# ffc_adapter.net
KiCad netlist of a schematic drawn in EAGLE
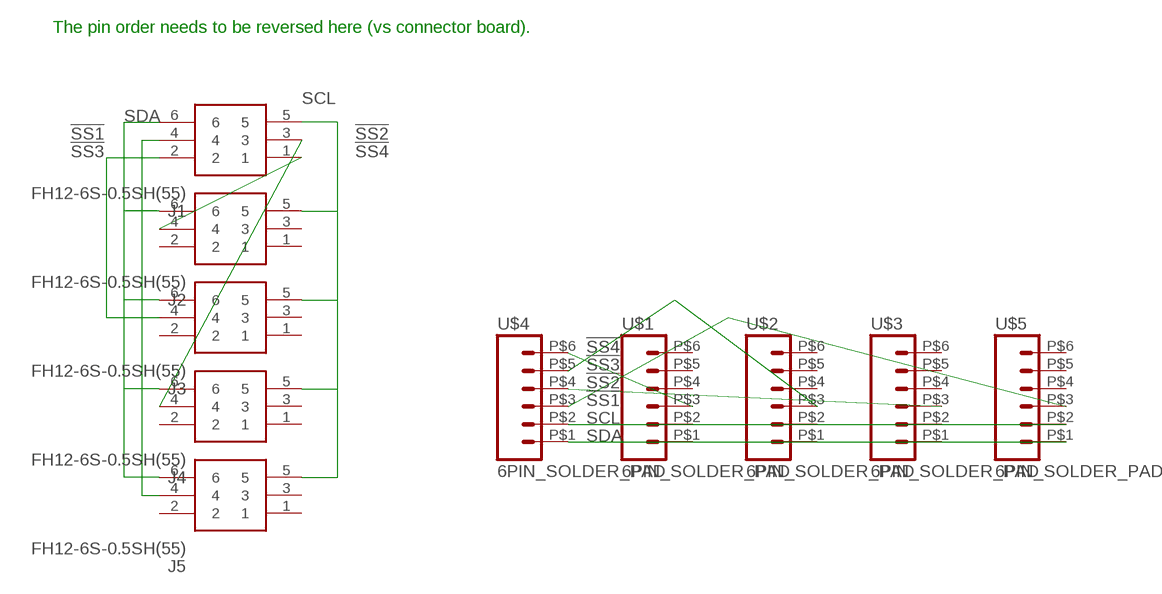
[diagram p0: schematic, sheet 1]

(export (version "E")
  (design (tool "Eeschema 10.0.6"))
  (components
    (comp (ref "J1")
      (value "FH12-6S-0.5SH(55)")
      (footprint "eagle-import:FH12-6S-0.5SH(55)_1")
      (fields
        (field (name "MOUSER_PART_NUMBER") "798-FH12-6S-0.5SH55")
        (field (name "RS_PART_NUMBER") "7388811P")
      )
      (libsource (lib "eagle-import") (part "FH12-6S-0.5SH(55)"))
    )
    (comp (ref "J2")
      (value "FH12-6S-0.5SH(55)")
      (footprint "eagle-import:FH12-6S-0.5SH(55)_1")
      (fields
        (field (name "MOUSER_PART_NUMBER") "798-FH12-6S-0.5SH55")
        (field (name "RS_PART_NUMBER") "7388811P")
      )
      (libsource (lib "eagle-import") (part "FH12-6S-0.5SH(55)"))
    )
    (comp (ref "J3")
      (value "FH12-6S-0.5SH(55)")
      (footprint "eagle-import:FH12-6S-0.5SH(55)_1")
      (fields
        (field (name "MOUSER_PART_NUMBER") "798-FH12-6S-0.5SH55")
        (field (name "RS_PART_NUMBER") "7388811P")
      )
      (libsource (lib "eagle-import") (part "FH12-6S-0.5SH(55)"))
    )
    (comp (ref "J4")
      (value "FH12-6S-0.5SH(55)")
      (footprint "eagle-import:FH12-6S-0.5SH(55)_1")
      (fields
        (field (name "MOUSER_PART_NUMBER") "798-FH12-6S-0.5SH55")
        (field (name "RS_PART_NUMBER") "7388811P")
      )
      (libsource (lib "eagle-import") (part "FH12-6S-0.5SH(55)"))
    )
    (comp (ref "J5")
      (value "FH12-6S-0.5SH(55)")
      (footprint "eagle-import:FH12-6S-0.5SH(55)_1")
      (fields
        (field (name "MOUSER_PART_NUMBER") "798-FH12-6S-0.5SH55")
        (field (name "RS_PART_NUMBER") "7388811P")
      )
      (libsource (lib "eagle-import") (part "FH12-6S-0.5SH(55)"))
    )
    (comp (ref "U$1")
      (value "6PIN_SOLDER_PAD")
      (footprint "eagle-import:6PIN_SOLDER_PAD")
      (libsource (lib "eagle-import") (part "6PIN_SOLDER_PAD"))
    )
    (comp (ref "U$2")
      (value "6PIN_SOLDER_PAD")
      (footprint "eagle-import:6PIN_SOLDER_PAD")
      (libsource (lib "eagle-import") (part "6PIN_SOLDER_PAD"))
    )
    (comp (ref "U$3")
      (value "6PIN_SOLDER_PAD")
      (footprint "eagle-import:6PIN_SOLDER_PAD")
      (libsource (lib "eagle-import") (part "6PIN_SOLDER_PAD"))
    )
    (comp (ref "U$4")
      (value "6PIN_SOLDER_PAD")
      (footprint "eagle-import:6PIN_SOLDER_PAD")
      (libsource (lib "eagle-import") (part "6PIN_SOLDER_PAD"))
    )
    (comp (ref "U$5")
      (value "6PIN_SOLDER_PAD")
      (footprint "eagle-import:6PIN_SOLDER_PAD")
      (libsource (lib "eagle-import") (part "6PIN_SOLDER_PAD"))
    )
  )
  (nets
    (net (code "1") (name "/SCL") (class "Default")
      (node (ref "J1") (pin "5") (pinfunction "5_5") (pintype "bidirectional"))
      (node (ref "J2") (pin "5") (pinfunction "5_5") (pintype "bidirectional"))
      (node (ref "J3") (pin "5") (pinfunction "5_5") (pintype "bidirectional"))
      (node (ref "J4") (pin "5") (pinfunction "5_5") (pintype "bidirectional"))
      (node (ref "J5") (pin "5") (pinfunction "5_5") (pintype "bidirectional"))
      (node (ref "U$1") (pin "P$2") (pinfunction "2_P$2") (pintype "passive"))
      (node (ref "U$2") (pin "P$2") (pinfunction "2_P$2") (pintype "passive"))
      (node (ref "U$3") (pin "P$2") (pinfunction "2_P$2") (pintype "passive"))
      (node (ref "U$4") (pin "P$2") (pinfunction "2_P$2") (pintype "passive"))
      (node (ref "U$5") (pin "P$2") (pinfunction "2_P$2") (pintype "passive"))
    )
    (net (code "2") (name "/SDA") (class "Default")
      (node (ref "J1") (pin "6") (pinfunction "6_6") (pintype "bidirectional"))
      (node (ref "J2") (pin "6") (pinfunction "6_6") (pintype "bidirectional"))
      (node (ref "J3") (pin "6") (pinfunction "6_6") (pintype "bidirectional"))
      (node (ref "J4") (pin "6") (pinfunction "6_6") (pintype "bidirectional"))
      (node (ref "J5") (pin "6") (pinfunction "6_6") (pintype "bidirectional"))
      (node (ref "U$1") (pin "P$1") (pinfunction "1_P$1") (pintype "passive"))
      (node (ref "U$2") (pin "P$1") (pinfunction "1_P$1") (pintype "passive"))
      (node (ref "U$3") (pin "P$1") (pinfunction "1_P$1") (pintype "passive"))
      (node (ref "U$4") (pin "P$1") (pinfunction "1_P$1") (pintype "passive"))
      (node (ref "U$5") (pin "P$1") (pinfunction "1_P$1") (pintype "passive"))
    )
    (net (code "3") (name "/~{SS1}") (class "Default")
      (node (ref "J1") (pin "4") (pinfunction "4_4") (pintype "bidirectional"))
      (node (ref "J5") (pin "4") (pinfunction "4_4") (pintype "bidirectional"))
      (node (ref "U$4") (pin "P$3") (pinfunction "3_P$3") (pintype "passive"))
      (node (ref "U$5") (pin "P$3") (pinfunction "3_P$3") (pintype "passive"))
    )
    (net (code "4") (name "/~{SS2}") (class "Default")
      (node (ref "J1") (pin "3") (pinfunction "3_3") (pintype "bidirectional"))
      (node (ref "J4") (pin "4") (pinfunction "4_4") (pintype "bidirectional"))
      (node (ref "U$3") (pin "P$3") (pinfunction "3_P$3") (pintype "passive"))
      (node (ref "U$4") (pin "P$4") (pinfunction "4_P$4") (pintype "passive"))
    )
    (net (code "5") (name "/~{SS3}") (class "Default")
      (node (ref "J1") (pin "2") (pinfunction "2_2") (pintype "bidirectional"))
      (node (ref "J3") (pin "4") (pinfunction "4_4") (pintype "bidirectional"))
      (node (ref "U$2") (pin "P$3") (pinfunction "3_P$3") (pintype "passive"))
      (node (ref "U$4") (pin "P$5") (pinfunction "5_P$5") (pintype "passive"))
    )
    (net (code "6") (name "/~{SS4}") (class "Default")
      (node (ref "J1") (pin "1") (pinfunction "1_1") (pintype "bidirectional"))
      (node (ref "J2") (pin "4") (pinfunction "4_4") (pintype "bidirectional"))
      (node (ref "U$1") (pin "P$3") (pinfunction "3_P$3") (pintype "passive"))
      (node (ref "U$4") (pin "P$6") (pinfunction "6_P$6") (pintype "passive"))
    )
    (net (code "7") (name "unconnected-(J2-Pad1)") (class "Default")
      (node (ref "J2") (pin "1") (pinfunction "1_1") (pintype "bidirectional"))
    )
    (net (code "8") (name "unconnected-(J2-Pad2)") (class "Default")
      (node (ref "J2") (pin "2") (pinfunction "2_2") (pintype "bidirectional"))
    )
    (net (code "9") (name "unconnected-(J2-Pad3)") (class "Default")
      (node (ref "J2") (pin "3") (pinfunction "3_3") (pintype "bidirectional"))
    )
    (net (code "10") (name "unconnected-(J3-Pad1)") (class "Default")
      (node (ref "J3") (pin "1") (pinfunction "1_1") (pintype "bidirectional"))
    )
    (net (code "11") (name "unconnected-(J3-Pad2)") (class "Default")
      (node (ref "J3") (pin "2") (pinfunction "2_2") (pintype "bidirectional"))
    )
    (net (code "12") (name "unconnected-(J3-Pad3)") (class "Default")
      (node (ref "J3") (pin "3") (pinfunction "3_3") (pintype "bidirectional"))
    )
    (net (code "13") (name "unconnected-(J4-Pad1)") (class "Default")
      (node (ref "J4") (pin "1") (pinfunction "1_1") (pintype "bidirectional"))
    )
    (net (code "14") (name "unconnected-(J4-Pad2)") (class "Default")
      (node (ref "J4") (pin "2") (pinfunction "2_2") (pintype "bidirectional"))
    )
    (net (code "15") (name "unconnected-(J4-Pad3)") (class "Default")
      (node (ref "J4") (pin "3") (pinfunction "3_3") (pintype "bidirectional"))
    )
    (net (code "16") (name "unconnected-(J5-Pad1)") (class "Default")
      (node (ref "J5") (pin "1") (pinfunction "1_1") (pintype "bidirectional"))
    )
    (net (code "17") (name "unconnected-(J5-Pad2)") (class "Default")
      (node (ref "J5") (pin "2") (pinfunction "2_2") (pintype "bidirectional"))
    )
    (net (code "18") (name "unconnected-(J5-Pad3)") (class "Default")
      (node (ref "J5") (pin "3") (pinfunction "3_3") (pintype "bidirectional"))
    )
    (net (code "19") (name "unconnected-(U$1-4-PadP$4)") (class "Default")
      (node (ref "U$1") (pin "P$4") (pinfunction "4_P$4") (pintype "passive"))
    )
    (net (code "20") (name "unconnected-(U$1-5-PadP$5)") (class "Default")
      (node (ref "U$1") (pin "P$5") (pinfunction "5_P$5") (pintype "passive"))
    )
    (net (code "21") (name "unconnected-(U$1-6-PadP$6)") (class "Default")
      (node (ref "U$1") (pin "P$6") (pinfunction "6_P$6") (pintype "passive"))
    )
    (net (code "22") (name "unconnected-(U$2-4-PadP$4)") (class "Default")
      (node (ref "U$2") (pin "P$4") (pinfunction "4_P$4") (pintype "passive"))
    )
    (net (code "23") (name "unconnected-(U$2-5-PadP$5)") (class "Default")
      (node (ref "U$2") (pin "P$5") (pinfunction "5_P$5") (pintype "passive"))
    )
    (net (code "24") (name "unconnected-(U$2-6-PadP$6)") (class "Default")
      (node (ref "U$2") (pin "P$6") (pinfunction "6_P$6") (pintype "passive"))
    )
    (net (code "25") (name "unconnected-(U$3-4-PadP$4)") (class "Default")
      (node (ref "U$3") (pin "P$4") (pinfunction "4_P$4") (pintype "passive"))
    )
    (net (code "26") (name "unconnected-(U$3-5-PadP$5)") (class "Default")
      (node (ref "U$3") (pin "P$5") (pinfunction "5_P$5") (pintype "passive"))
    )
    (net (code "27") (name "unconnected-(U$3-6-PadP$6)") (class "Default")
      (node (ref "U$3") (pin "P$6") (pinfunction "6_P$6") (pintype "passive"))
    )
    (net (code "28") (name "unconnected-(U$5-4-PadP$4)") (class "Default")
      (node (ref "U$5") (pin "P$4") (pinfunction "4_P$4") (pintype "passive"))
    )
    (net (code "29") (name "unconnected-(U$5-5-PadP$5)") (class "Default")
      (node (ref "U$5") (pin "P$5") (pinfunction "5_P$5") (pintype "passive"))
    )
    (net (code "30") (name "unconnected-(U$5-6-PadP$6)") (class "Default")
      (node (ref "U$5") (pin "P$6") (pinfunction "6_P$6") (pintype "passive"))
    )
  )
)
